# Bank13.net
KiCad netlist of a schematic drawn in Altium Designer
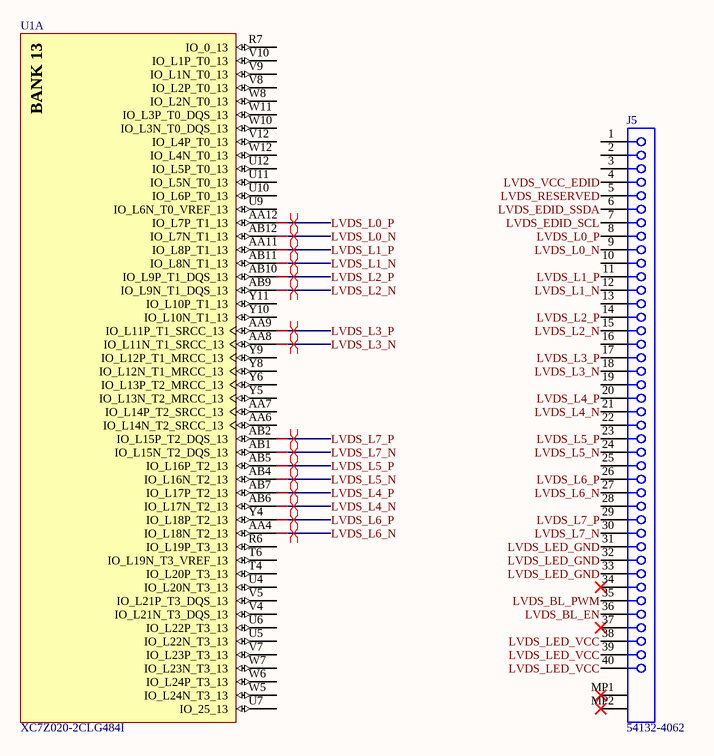
[diagram p0: Bank13.SchDoc]

(export (version "E")
  (design (tool "Eeschema 10.0.6"))
  (components
    (comp (ref "J5")
      (value "54132-4062")
      (footprint "MOLX-54132-4062")
      (fields (field (name "MANUFACTURER") "Molex"))
      (libsource (lib "Altium Content Vault") (part "MOLX-54132-4062"))
    )
    (comp (ref "U1")
      (value "XC7Z020-2CLG484I")
      (footprint "CLG484")
      (fields (field (name "GENERIC PART NUMBER") "XC7Z020"))
      (libsource (lib "Altium Content Vault") (part "XNLX-XC7Z020-CLG484"))
    )
  )
  (nets
    (net (code "1") (name "/LVDS_BL_EN") (class "Default")
      (node (ref "J5") (pin "36") (pinfunction "36_36") (pintype "passive"))
    )
    (net (code "2") (name "/LVDS_BL_PWM") (class "Default")
      (node (ref "J5") (pin "35") (pinfunction "35_35") (pintype "passive"))
    )
    (net (code "3") (name "/LVDS_EDID_SCL") (class "Default")
      (node (ref "J5") (pin "7") (pinfunction "7_7") (pintype "passive"))
    )
    (net (code "4") (name "/LVDS_EDID_SSDA") (class "Default")
      (node (ref "J5") (pin "6") (pinfunction "6_6") (pintype "passive"))
    )
    (net (code "5") (name "/LVDS_L0_N") (class "Default")
      (node (ref "J5") (pin "9") (pinfunction "9_9") (pintype "passive"))
      (node (ref "U1") (pin "AB12") (pinfunction "IO_L7N_T1_13_AB12") (pintype "bidirectional"))
    )
    (net (code "6") (name "/LVDS_L0_P") (class "Default")
      (node (ref "J5") (pin "8") (pinfunction "8_8") (pintype "passive"))
      (node (ref "U1") (pin "AA12") (pinfunction "IO_L7P_T1_13_AA12") (pintype "bidirectional"))
    )
    (net (code "7") (name "/LVDS_L1_N") (class "Default")
      (node (ref "J5") (pin "12") (pinfunction "12_12") (pintype "passive"))
      (node (ref "U1") (pin "AB11") (pinfunction "IO_L8N_T1_13_AB11") (pintype "bidirectional"))
    )
    (net (code "8") (name "/LVDS_L1_P") (class "Default")
      (node (ref "J5") (pin "11") (pinfunction "11_11") (pintype "passive"))
      (node (ref "U1") (pin "AA11") (pinfunction "IO_L8P_T1_13_AA11") (pintype "bidirectional"))
    )
    (net (code "9") (name "/LVDS_L2_N") (class "Default")
      (node (ref "J5") (pin "15") (pinfunction "15_15") (pintype "passive"))
      (node (ref "U1") (pin "AB9") (pinfunction "IO_L9N_T1_DQS_13_AB9") (pintype "bidirectional"))
    )
    (net (code "10") (name "/LVDS_L2_P") (class "Default")
      (node (ref "J5") (pin "14") (pinfunction "14_14") (pintype "passive"))
      (node (ref "U1") (pin "AB10") (pinfunction "IO_L9P_T1_DQS_13_AB10") (pintype "bidirectional"))
    )
    (net (code "11") (name "/LVDS_L3_N") (class "Default")
      (node (ref "J5") (pin "18") (pinfunction "18_18") (pintype "passive"))
      (node (ref "U1") (pin "AA8") (pinfunction "IO_L11N_T1_SRCC_13_AA8") (pintype "bidirectional"))
    )
    (net (code "12") (name "/LVDS_L3_P") (class "Default")
      (node (ref "J5") (pin "17") (pinfunction "17_17") (pintype "passive"))
      (node (ref "U1") (pin "AA9") (pinfunction "IO_L11P_T1_SRCC_13_AA9") (pintype "bidirectional"))
    )
    (net (code "13") (name "/LVDS_L4_N") (class "Default")
      (node (ref "J5") (pin "21") (pinfunction "21_21") (pintype "passive"))
      (node (ref "U1") (pin "AB6") (pinfunction "IO_L17N_T2_13_AB6") (pintype "bidirectional"))
    )
    (net (code "14") (name "/LVDS_L4_P") (class "Default")
      (node (ref "J5") (pin "20") (pinfunction "20_20") (pintype "passive"))
      (node (ref "U1") (pin "AB7") (pinfunction "IO_L17P_T2_13_AB7") (pintype "bidirectional"))
    )
    (net (code "15") (name "/LVDS_L5_N") (class "Default")
      (node (ref "J5") (pin "24") (pinfunction "24_24") (pintype "passive"))
      (node (ref "U1") (pin "AB4") (pinfunction "IO_L16N_T2_13_AB4") (pintype "bidirectional"))
    )
    (net (code "16") (name "/LVDS_L5_P") (class "Default")
      (node (ref "J5") (pin "23") (pinfunction "23_23") (pintype "passive"))
      (node (ref "U1") (pin "AB5") (pinfunction "IO_L16P_T2_13_AB5") (pintype "bidirectional"))
    )
    (net (code "17") (name "/LVDS_L6_N") (class "Default")
      (node (ref "J5") (pin "27") (pinfunction "27_27") (pintype "passive"))
      (node (ref "U1") (pin "AA4") (pinfunction "IO_L18N_T2_13_AA4") (pintype "bidirectional"))
    )
    (net (code "18") (name "/LVDS_L6_P") (class "Default")
      (node (ref "J5") (pin "26") (pinfunction "26_26") (pintype "passive"))
      (node (ref "U1") (pin "Y4") (pinfunction "IO_L18P_T2_13_Y4") (pintype "bidirectional"))
    )
    (net (code "19") (name "/LVDS_L7_N") (class "Default")
      (node (ref "J5") (pin "30") (pinfunction "30_30") (pintype "passive"))
      (node (ref "U1") (pin "AB1") (pinfunction "IO_L15N_T2_DQS_13_AB1") (pintype "bidirectional"))
    )
    (net (code "20") (name "/LVDS_L7_P") (class "Default")
      (node (ref "J5") (pin "29") (pinfunction "29_29") (pintype "passive"))
      (node (ref "U1") (pin "AB2") (pinfunction "IO_L15P_T2_DQS_13_AB2") (pintype "bidirectional"))
    )
    (net (code "21") (name "/LVDS_LED_GND") (class "Default")
      (node (ref "J5") (pin "31") (pinfunction "31_31") (pintype "passive"))
      (node (ref "J5") (pin "32") (pinfunction "32_32") (pintype "passive"))
      (node (ref "J5") (pin "33") (pinfunction "33_33") (pintype "passive"))
    )
    (net (code "22") (name "/LVDS_LED_VCC") (class "Default")
      (node (ref "J5") (pin "38") (pinfunction "38_38") (pintype "passive"))
      (node (ref "J5") (pin "39") (pinfunction "39_39") (pintype "passive"))
      (node (ref "J5") (pin "40") (pinfunction "40_40") (pintype "passive"))
    )
    (net (code "23") (name "/LVDS_RESERVED") (class "Default")
      (node (ref "J5") (pin "5") (pinfunction "5_5") (pintype "passive"))
    )
    (net (code "24") (name "/LVDS_VCC_EDID") (class "Default")
      (node (ref "J5") (pin "4") (pinfunction "4_4") (pintype "passive"))
    )
    (net (code "25") (name "unconnected-(J5-Pad1)") (class "Default")
      (node (ref "J5") (pin "1") (pinfunction "1_1") (pintype "passive"))
    )
    (net (code "26") (name "unconnected-(J5-Pad2)") (class "Default")
      (node (ref "J5") (pin "2") (pinfunction "2_2") (pintype "passive"))
    )
    (net (code "27") (name "unconnected-(J5-Pad3)") (class "Default")
      (node (ref "J5") (pin "3") (pinfunction "3_3") (pintype "passive"))
    )
    (net (code "28") (name "unconnected-(J5-Pad10)") (class "Default")
      (node (ref "J5") (pin "10") (pinfunction "10_10") (pintype "passive"))
    )
    (net (code "29") (name "unconnected-(J5-Pad13)") (class "Default")
      (node (ref "J5") (pin "13") (pinfunction "13_13") (pintype "passive"))
    )
    (net (code "30") (name "unconnected-(J5-Pad16)") (class "Default")
      (node (ref "J5") (pin "16") (pinfunction "16_16") (pintype "passive"))
    )
    (net (code "31") (name "unconnected-(J5-Pad19)") (class "Default")
      (node (ref "J5") (pin "19") (pinfunction "19_19") (pintype "passive"))
    )
    (net (code "32") (name "unconnected-(J5-Pad22)") (class "Default")
      (node (ref "J5") (pin "22") (pinfunction "22_22") (pintype "passive"))
    )
    (net (code "33") (name "unconnected-(J5-Pad25)") (class "Default")
      (node (ref "J5") (pin "25") (pinfunction "25_25") (pintype "passive"))
    )
    (net (code "34") (name "unconnected-(J5-Pad28)") (class "Default")
      (node (ref "J5") (pin "28") (pinfunction "28_28") (pintype "passive"))
    )
    (net (code "35") (name "unconnected-(J5-Pad34)") (class "Default")
      (node (ref "J5") (pin "34") (pinfunction "34_34") (pintype "passive+no_connect"))
    )
    (net (code "36") (name "unconnected-(J5-Pad37)") (class "Default")
      (node (ref "J5") (pin "37") (pinfunction "37_37") (pintype "passive+no_connect"))
    )
    (net (code "37") (name "unconnected-(J5-PadMP1)") (class "Default")
      (node (ref "J5") (pin "MP1") (pinfunction "MP1_MP1") (pintype "passive+no_connect"))
    )
    (net (code "38") (name "unconnected-(J5-PadMP2)") (class "Default")
      (node (ref "J5") (pin "MP2") (pinfunction "MP2_MP2") (pintype "passive+no_connect"))
    )
    (net (code "39") (name "unconnected-(U1A-IO_0_13-PadR7)") (class "Default")
      (node (ref "U1") (pin "R7") (pinfunction "IO_0_13_R7") (pintype "bidirectional"))
    )
    (net (code "40") (name "unconnected-(U1A-IO_25_13-PadU7)") (class "Default")
      (node (ref "U1") (pin "U7") (pinfunction "IO_25_13_U7") (pintype "bidirectional"))
    )
    (net (code "41") (name "unconnected-(U1A-IO_L1N_T0_13-PadV9)") (class "Default")
      (node (ref "U1") (pin "V9") (pinfunction "IO_L1N_T0_13_V9") (pintype "bidirectional"))
    )
    (net (code "42") (name "unconnected-(U1A-IO_L1P_T0_13-PadV10)") (class "Default")
      (node (ref "U1") (pin "V10") (pinfunction "IO_L1P_T0_13_V10") (pintype "bidirectional"))
    )
    (net (code "43") (name "unconnected-(U1A-IO_L2N_T0_13-PadW8)") (class "Default")
      (node (ref "U1") (pin "W8") (pinfunction "IO_L2N_T0_13_W8") (pintype "bidirectional"))
    )
    (net (code "44") (name "unconnected-(U1A-IO_L2P_T0_13-PadV8)") (class "Default")
      (node (ref "U1") (pin "V8") (pinfunction "IO_L2P_T0_13_V8") (pintype "bidirectional"))
    )
    (net (code "45") (name "unconnected-(U1A-IO_L3N_T0_DQS_13-PadW10)") (class "Default")
      (node (ref "U1") (pin "W10") (pinfunction "IO_L3N_T0_DQS_13_W10") (pintype "bidirectional"))
    )
    (net (code "46") (name "unconnected-(U1A-IO_L3P_T0_DQS_13-PadW11)") (class "Default")
      (node (ref "U1") (pin "W11") (pinfunction "IO_L3P_T0_DQS_13_W11") (pintype "bidirectional"))
    )
    (net (code "47") (name "unconnected-(U1A-IO_L4N_T0_13-PadW12)") (class "Default")
      (node (ref "U1") (pin "W12") (pinfunction "IO_L4N_T0_13_W12") (pintype "bidirectional"))
    )
    (net (code "48") (name "unconnected-(U1A-IO_L4P_T0_13-PadV12)") (class "Default")
      (node (ref "U1") (pin "V12") (pinfunction "IO_L4P_T0_13_V12") (pintype "bidirectional"))
    )
    (net (code "49") (name "unconnected-(U1A-IO_L5N_T0_13-PadU11)") (class "Default")
      (node (ref "U1") (pin "U11") (pinfunction "IO_L5N_T0_13_U11") (pintype "bidirectional"))
    )
    (net (code "50") (name "unconnected-(U1A-IO_L5P_T0_13-PadU12)") (class "Default")
      (node (ref "U1") (pin "U12") (pinfunction "IO_L5P_T0_13_U12") (pintype "bidirectional"))
    )
    (net (code "51") (name "unconnected-(U1A-IO_L6N_T0_VREF_13-PadU9)") (class "Default")
      (node (ref "U1") (pin "U9") (pinfunction "IO_L6N_T0_VREF_13_U9") (pintype "bidirectional"))
    )
    (net (code "52") (name "unconnected-(U1A-IO_L6P_T0_13-PadU10)") (class "Default")
      (node (ref "U1") (pin "U10") (pinfunction "IO_L6P_T0_13_U10") (pintype "bidirectional"))
    )
    (net (code "53") (name "unconnected-(U1A-IO_L10N_T1_13-PadY10)") (class "Default")
      (node (ref "U1") (pin "Y10") (pinfunction "IO_L10N_T1_13_Y10") (pintype "bidirectional"))
    )
    (net (code "54") (name "unconnected-(U1A-IO_L10P_T1_13-PadY11)") (class "Default")
      (node (ref "U1") (pin "Y11") (pinfunction "IO_L10P_T1_13_Y11") (pintype "bidirectional"))
    )
    (net (code "55") (name "unconnected-(U1A-IO_L12N_T1_MRCC_13-PadY8)") (class "Default")
      (node (ref "U1") (pin "Y8") (pinfunction "IO_L12N_T1_MRCC_13_Y8") (pintype "bidirectional"))
    )
    (net (code "56") (name "unconnected-(U1A-IO_L12P_T1_MRCC_13-PadY9)") (class "Default")
      (node (ref "U1") (pin "Y9") (pinfunction "IO_L12P_T1_MRCC_13_Y9") (pintype "bidirectional"))
    )
    (net (code "57") (name "unconnected-(U1A-IO_L13N_T2_MRCC_13-PadY5)") (class "Default")
      (node (ref "U1") (pin "Y5") (pinfunction "IO_L13N_T2_MRCC_13_Y5") (pintype "bidirectional"))
    )
    (net (code "58") (name "unconnected-(U1A-IO_L13P_T2_MRCC_13-PadY6)") (class "Default")
      (node (ref "U1") (pin "Y6") (pinfunction "IO_L13P_T2_MRCC_13_Y6") (pintype "bidirectional"))
    )
    (net (code "59") (name "unconnected-(U1A-IO_L14N_T2_SRCC_13-PadAA6)") (class "Default")
      (node (ref "U1") (pin "AA6") (pinfunction "IO_L14N_T2_SRCC_13_AA6") (pintype "bidirectional"))
    )
    (net (code "60") (name "unconnected-(U1A-IO_L14P_T2_SRCC_13-PadAA7)") (class "Default")
      (node (ref "U1") (pin "AA7") (pinfunction "IO_L14P_T2_SRCC_13_AA7") (pintype "bidirectional"))
    )
    (net (code "61") (name "unconnected-(U1A-IO_L19N_T3_VREF_13-PadT6)") (class "Default")
      (node (ref "U1") (pin "T6") (pinfunction "IO_L19N_T3_VREF_13_T6") (pintype "bidirectional"))
    )
    (net (code "62") (name "unconnected-(U1A-IO_L19P_T3_13-PadR6)") (class "Default")
      (node (ref "U1") (pin "R6") (pinfunction "IO_L19P_T3_13_R6") (pintype "bidirectional"))
    )
    (net (code "63") (name "unconnected-(U1A-IO_L20N_T3_13-PadU4)") (class "Default")
      (node (ref "U1") (pin "U4") (pinfunction "IO_L20N_T3_13_U4") (pintype "bidirectional"))
    )
    (net (code "64") (name "unconnected-(U1A-IO_L20P_T3_13-PadT4)") (class "Default")
      (node (ref "U1") (pin "T4") (pinfunction "IO_L20P_T3_13_T4") (pintype "bidirectional"))
    )
    (net (code "65") (name "unconnected-(U1A-IO_L21N_T3_DQS_13-PadV4)") (class "Default")
      (node (ref "U1") (pin "V4") (pinfunction "IO_L21N_T3_DQS_13_V4") (pintype "bidirectional"))
    )
    (net (code "66") (name "unconnected-(U1A-IO_L21P_T3_DQS_13-PadV5)") (class "Default")
      (node (ref "U1") (pin "V5") (pinfunction "IO_L21P_T3_DQS_13_V5") (pintype "bidirectional"))
    )
    (net (code "67") (name "unconnected-(U1A-IO_L22N_T3_13-PadU5)") (class "Default")
      (node (ref "U1") (pin "U5") (pinfunction "IO_L22N_T3_13_U5") (pintype "bidirectional"))
    )
    (net (code "68") (name "unconnected-(U1A-IO_L22P_T3_13-PadU6)") (class "Default")
      (node (ref "U1") (pin "U6") (pinfunction "IO_L22P_T3_13_U6") (pintype "bidirectional"))
    )
    (net (code "69") (name "unconnected-(U1A-IO_L23N_T3_13-PadW7)") (class "Default")
      (node (ref "U1") (pin "W7") (pinfunction "IO_L23N_T3_13_W7") (pintype "bidirectional"))
    )
    (net (code "70") (name "unconnected-(U1A-IO_L23P_T3_13-PadV7)") (class "Default")
      (node (ref "U1") (pin "V7") (pinfunction "IO_L23P_T3_13_V7") (pintype "bidirectional"))
    )
    (net (code "71") (name "unconnected-(U1A-IO_L24N_T3_13-PadW5)") (class "Default")
      (node (ref "U1") (pin "W5") (pinfunction "IO_L24N_T3_13_W5") (pintype "bidirectional"))
    )
    (net (code "72") (name "unconnected-(U1A-IO_L24P_T3_13-PadW6)") (class "Default")
      (node (ref "U1") (pin "W6") (pinfunction "IO_L24P_T3_13_W6") (pintype "bidirectional"))
    )
  )
)
